# MCU.net
KiCad netlist of a schematic drawn in Altium Designer
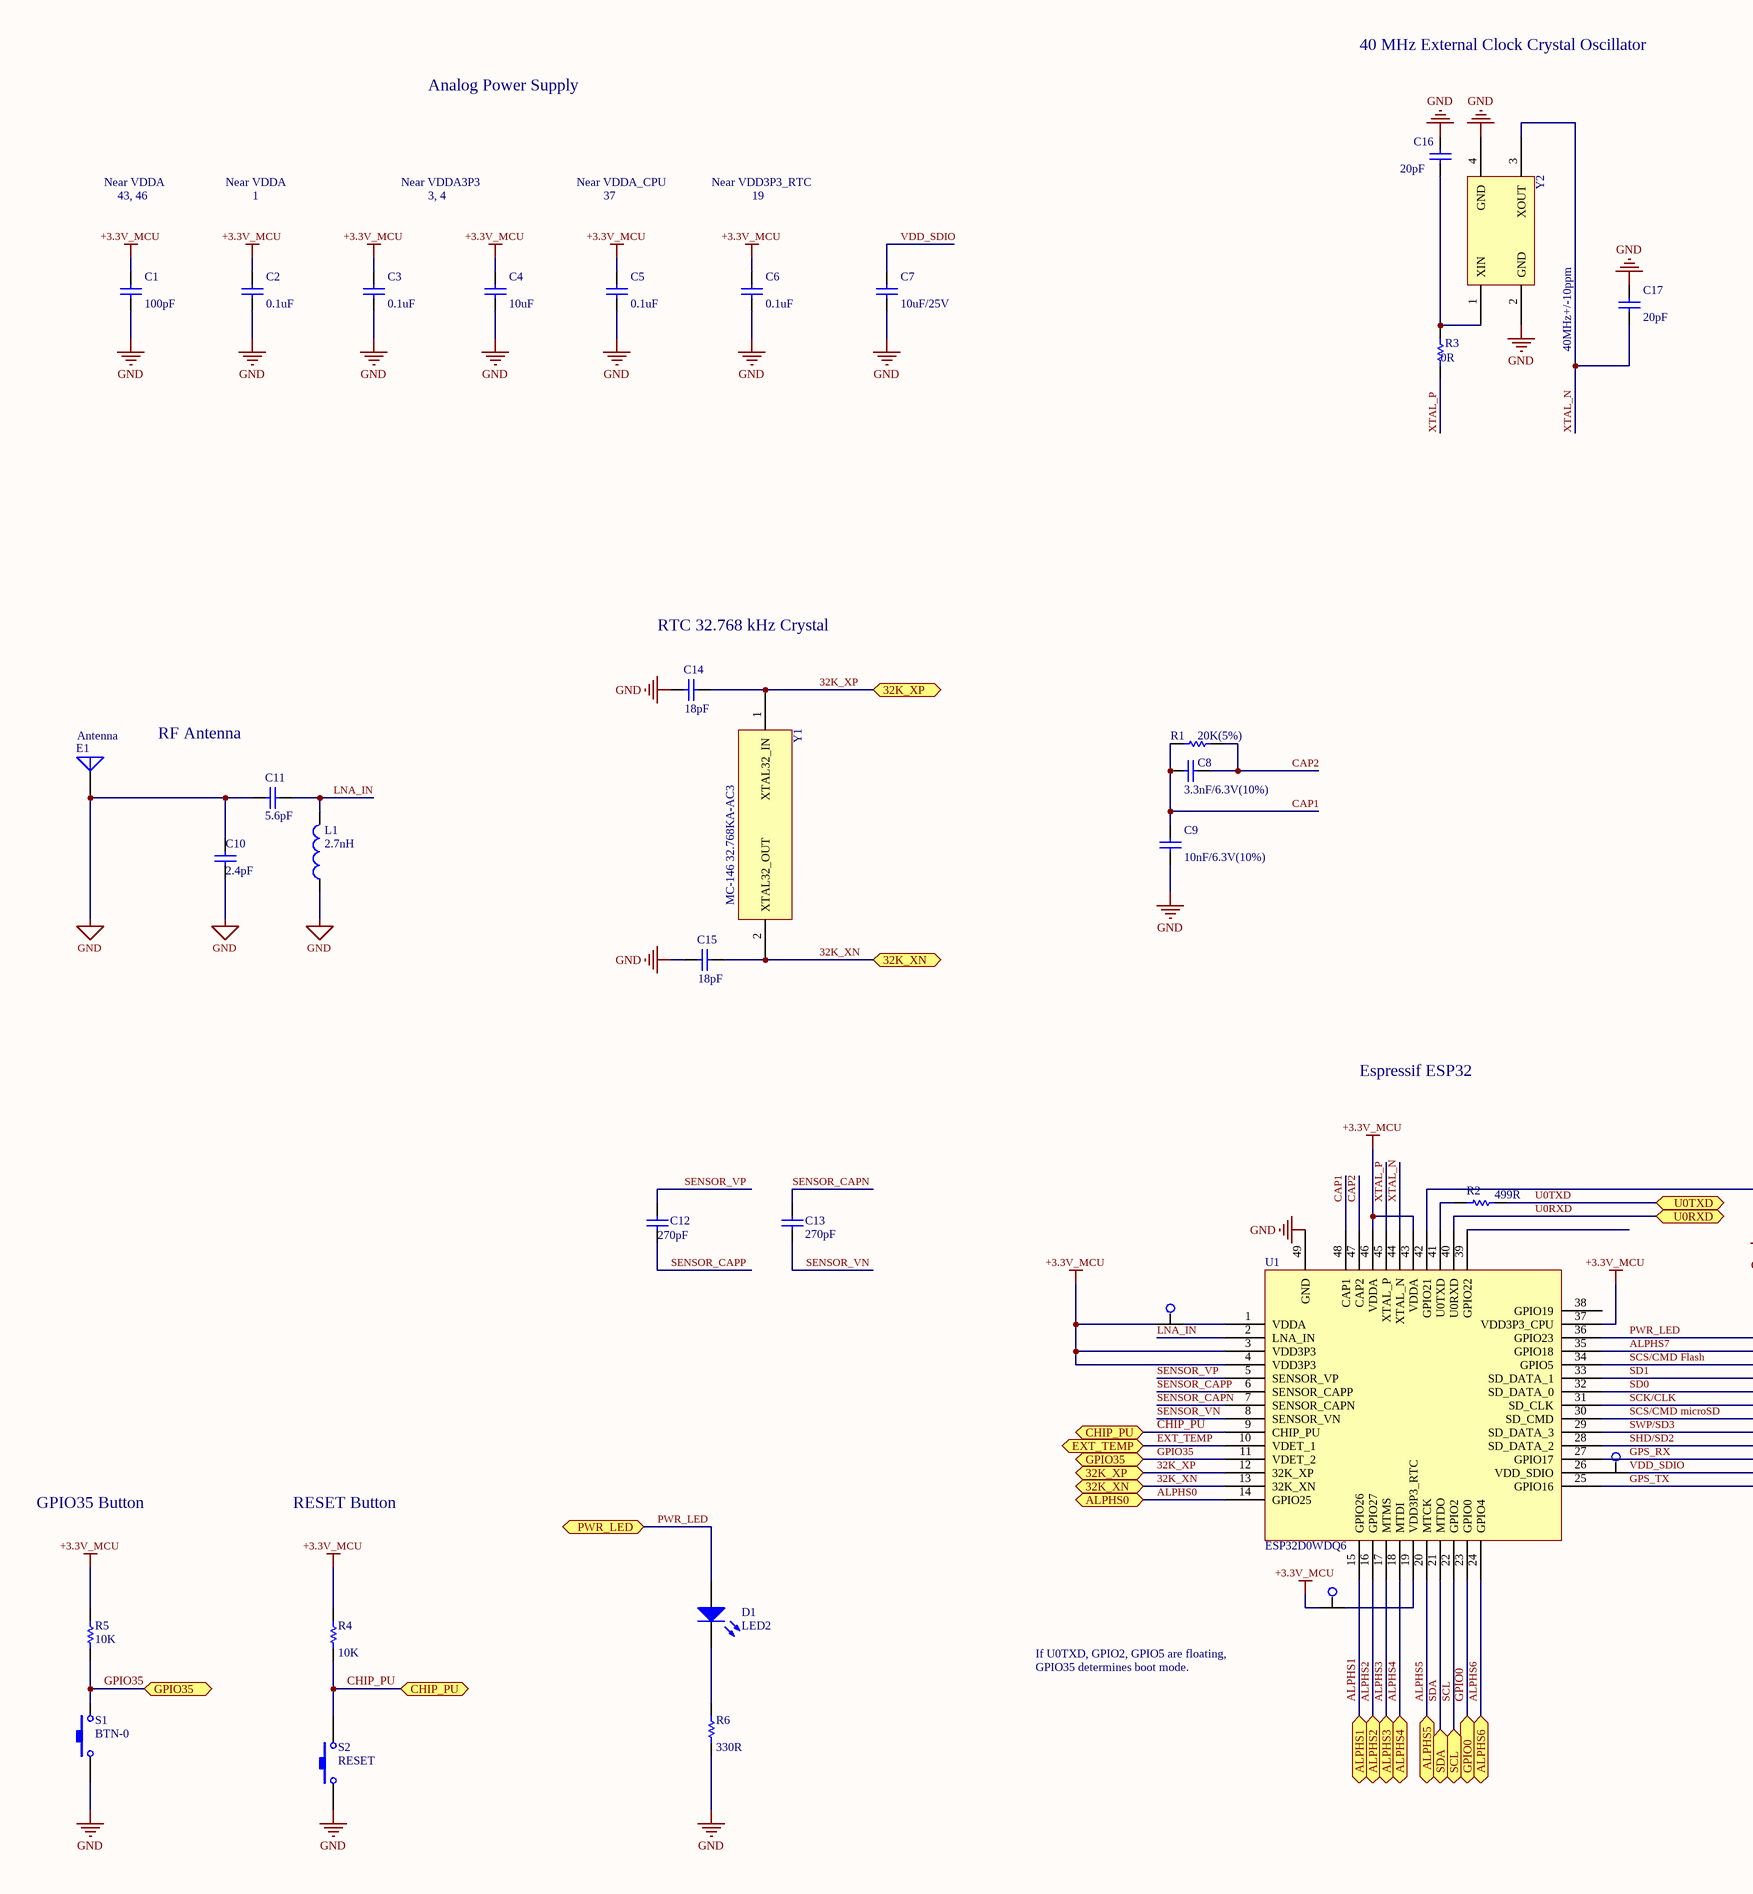
[diagram p0: MCU.SchDoc, left]
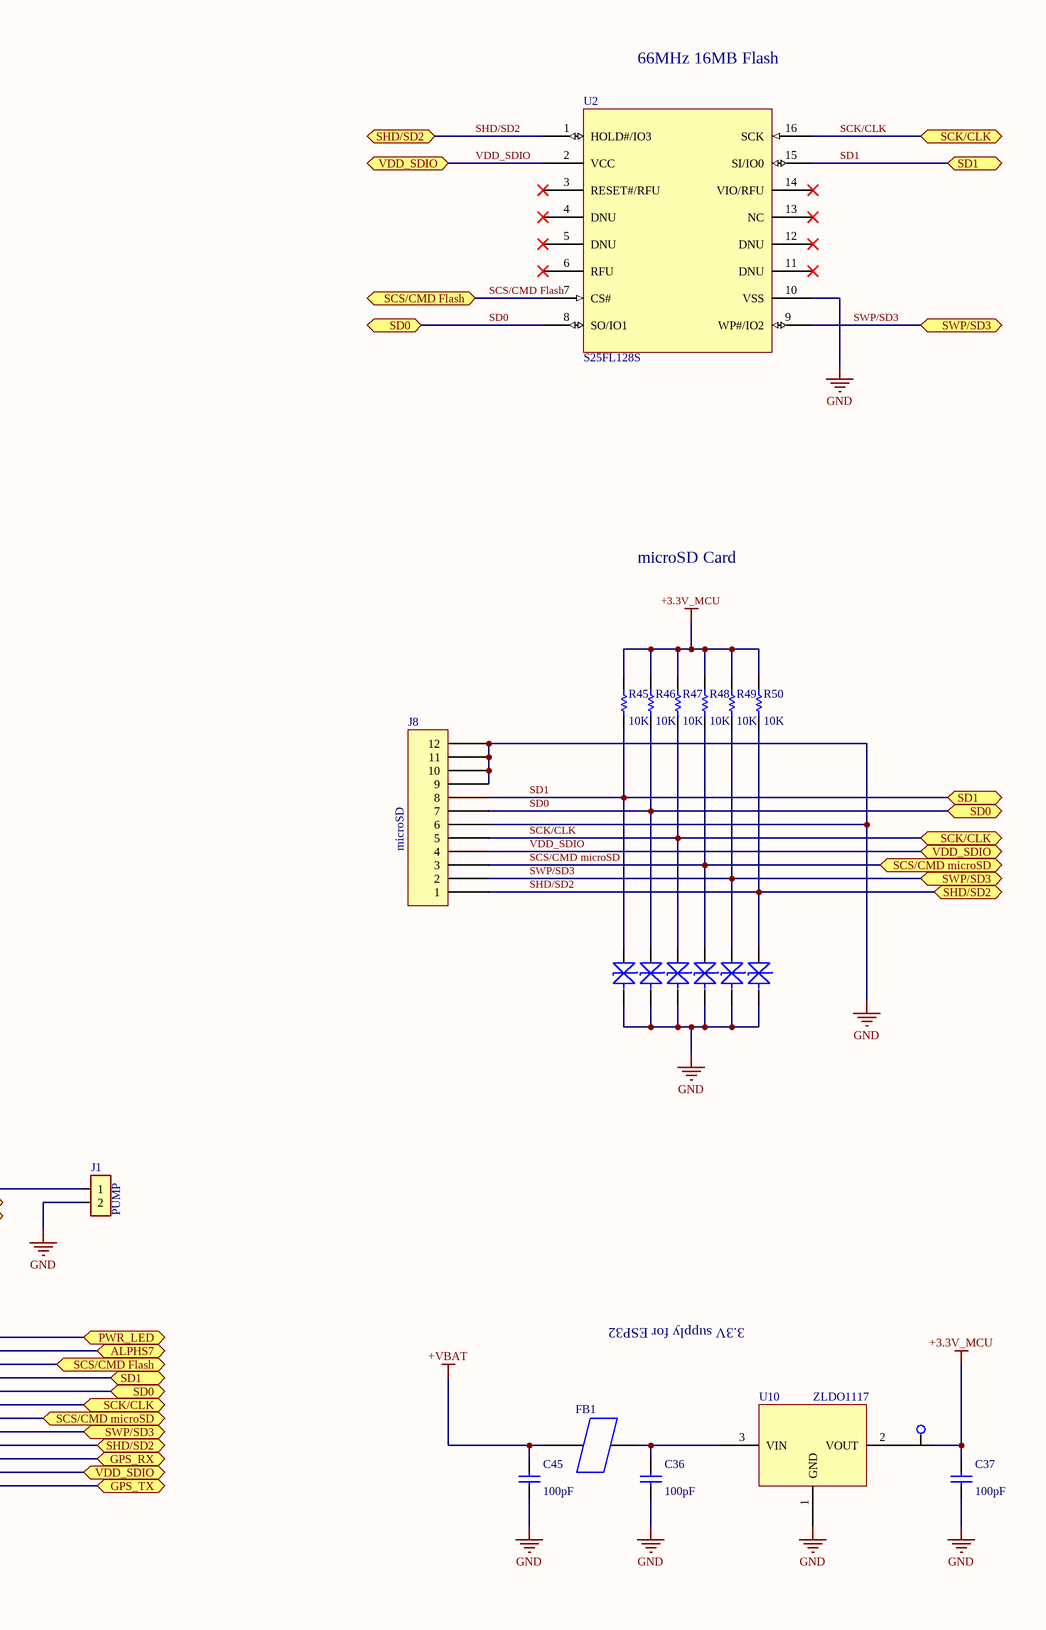
[diagram p1: MCU.SchDoc, right]

(export (version "E")
  (design (tool "Eeschema 10.0.6"))
  (components
    (comp (ref "C1")
      (value "100pF")
      (footprint "1608[0603]")
      (description "Capacitor")
      (fields (field (name "Comment") "Cap") (field (name "PUBLISHER") "Altium Limited"))
      (libsource (lib "Miscellaneous Devices") (part "Cap"))
    )
    (comp (ref "C2")
      (value "0.1uF")
      (footprint "1608[0603]")
      (description "Capacitor")
      (fields (field (name "Comment") "Cap") (field (name "PUBLISHER") "Altium Limited"))
      (libsource (lib "Miscellaneous Devices") (part "Cap"))
    )
    (comp (ref "C3")
      (value "0.1uF")
      (footprint "1608[0603]")
      (description "Capacitor")
      (fields (field (name "Comment") "Cap") (field (name "PUBLISHER") "Altium Limited"))
      (libsource (lib "Miscellaneous Devices") (part "Cap"))
    )
    (comp (ref "C4")
      (value "10uF")
      (footprint "1608[0603]")
      (description "Capacitor")
      (fields (field (name "Comment") "Cap") (field (name "PUBLISHER") "Altium Limited"))
      (libsource (lib "Miscellaneous Devices") (part "Cap"))
    )
    (comp (ref "C5")
      (value "0.1uF")
      (footprint "1608[0603]")
      (description "Capacitor")
      (fields (field (name "Comment") "Cap") (field (name "PUBLISHER") "Altium Limited"))
      (libsource (lib "Miscellaneous Devices") (part "Cap"))
    )
    (comp (ref "C6")
      (value "0.1uF")
      (footprint "1608[0603]")
      (description "Capacitor")
      (fields (field (name "Comment") "Cap") (field (name "PUBLISHER") "Altium Limited"))
      (libsource (lib "Miscellaneous Devices") (part "Cap"))
    )
    (comp (ref "C7")
      (value "10uF/25V")
      (footprint "1608[0603]")
      (description "Capacitor")
      (fields (field (name "Comment") "Cap") (field (name "PUBLISHER") "Altium Limited"))
      (libsource (lib "Miscellaneous Devices") (part "Cap"))
    )
    (comp (ref "C8")
      (value "3.3nF/6.3V(10%)")
      (footprint "1608[0603]")
      (description "Capacitor")
      (fields (field (name "Comment") "Cap") (field (name "PUBLISHER") "Altium Limited"))
      (libsource (lib "Miscellaneous Devices") (part "Cap"))
    )
    (comp (ref "C9")
      (value "10nF/6.3V(10%)")
      (footprint "1608[0603]")
      (description "Capacitor")
      (fields (field (name "Comment") "Cap") (field (name "PUBLISHER") "Altium Limited"))
      (libsource (lib "Miscellaneous Devices") (part "Cap"))
    )
    (comp (ref "C10")
      (value "2.4pF")
      (footprint "1608[0603]")
      (description "Capacitor")
      (fields (field (name "Comment") "Cap") (field (name "PUBLISHER") "Altium Limited"))
      (libsource (lib "Miscellaneous Devices") (part "Cap"))
    )
    (comp (ref "C11")
      (value "5.6pF")
      (footprint "1608[0603]")
      (description "Capacitor")
      (fields (field (name "Comment") "Cap") (field (name "PUBLISHER") "Altium Limited"))
      (libsource (lib "Miscellaneous Devices") (part "Cap"))
    )
    (comp (ref "C12")
      (value "270pF")
      (footprint "1608[0603]")
      (description "Capacitor")
      (fields (field (name "Comment") "Cap") (field (name "PUBLISHER") "Altium Limited"))
      (libsource (lib "Miscellaneous Devices") (part "Cap"))
    )
    (comp (ref "C13")
      (value "270pF")
      (footprint "1608[0603]")
      (description "Capacitor")
      (fields (field (name "Comment") "Cap") (field (name "PUBLISHER") "Altium Limited"))
      (libsource (lib "Miscellaneous Devices") (part "Cap"))
    )
    (comp (ref "C14")
      (value "18pF")
      (footprint "1608[0603]")
      (description "Capacitor")
      (fields (field (name "Comment") "Cap") (field (name "PUBLISHER") "Altium Limited"))
      (libsource (lib "Miscellaneous Devices") (part "Cap"))
    )
    (comp (ref "C15")
      (value "18pF")
      (footprint "1608[0603]")
      (description "Capacitor")
      (fields (field (name "Comment") "Cap") (field (name "PUBLISHER") "Altium Limited"))
      (libsource (lib "Miscellaneous Devices") (part "Cap"))
    )
    (comp (ref "C16")
      (value "20pF")
      (footprint "1608[0603]")
      (description "Capacitor")
      (fields (field (name "Comment") "Cap") (field (name "PUBLISHER") "Altium Limited"))
      (libsource (lib "Miscellaneous Devices") (part "Cap"))
    )
    (comp (ref "C17")
      (value "20pF")
      (footprint "1608[0603]")
      (description "Capacitor")
      (fields (field (name "Comment") "Cap") (field (name "PUBLISHER") "Altium Limited"))
      (libsource (lib "Miscellaneous Devices") (part "Cap"))
    )
    (comp (ref "C36")
      (value "100pF")
      (footprint "1608[0603]")
      (description "Capacitor")
      (fields (field (name "Comment") "Cap") (field (name "PUBLISHER") "Altium Limited"))
      (libsource (lib "Miscellaneous Devices") (part "Cap"))
    )
    (comp (ref "C37")
      (value "100pF")
      (footprint "1608[0603]")
      (description "Capacitor")
      (fields (field (name "Comment") "Cap") (field (name "PUBLISHER") "Altium Limited"))
      (libsource (lib "Miscellaneous Devices") (part "Cap"))
    )
    (comp (ref "C45")
      (value "100pF")
      (footprint "1608[0603]")
      (description "Capacitor")
      (fields (field (name "Comment") "Cap") (field (name "PUBLISHER") "Altium Limited"))
      (libsource (lib "Miscellaneous Devices") (part "Cap"))
    )
    (comp (ref "D1")
      (value "LED2")
      (footprint "3.2X1.6X1.1")
      (description "Typical RED, GREEN, YELLOW, AMBER GaAs LED")
      (fields (field (name "PUBLISHER") "Altium Limited"))
      (libsource (lib "Miscellaneous Devices") (part "LED2"))
    )
    (comp (ref "D4")
      (value "ESD7951ST5GOSCT-ND")
      (footprint "SODFL100X40-2N")
      (description "TVS Diode")
      (libsource (lib "Gas Monitor Components") (part "ESD7951S"))
    )
    (comp (ref "D5")
      (value "ESD7951ST5GOSCT-ND")
      (footprint "SODFL100X40-2N")
      (description "TVS Diode")
      (libsource (lib "Gas Monitor Components") (part "ESD7951S"))
    )
    (comp (ref "D6")
      (value "ESD7951ST5GOSCT-ND")
      (footprint "SODFL100X40-2N")
      (description "TVS Diode")
      (libsource (lib "Gas Monitor Components") (part "ESD7951S"))
    )
    (comp (ref "D7")
      (value "ESD7951ST5GOSCT-ND")
      (footprint "SODFL100X40-2N")
      (description "TVS Diode")
      (libsource (lib "Gas Monitor Components") (part "ESD7951S"))
    )
    (comp (ref "D8")
      (value "ESD7951ST5GOSCT-ND")
      (footprint "SODFL100X40-2N")
      (description "TVS Diode")
      (libsource (lib "Gas Monitor Components") (part "ESD7951S"))
    )
    (comp (ref "D9")
      (value "ESD7951ST5GOSCT-ND")
      (footprint "SODFL100X40-2N")
      (description "TVS Diode")
      (libsource (lib "Gas Monitor Components") (part "ESD7951S"))
    )
    (comp (ref "E1")
      (value "Antenna")
      (footprint "SWRA1117")
      (description "Generic Antenna")
      (fields (field (name "PUBLISHER") "Altium Limited"))
      (libsource (lib "Miscellaneous Devices") (part "Antenna"))
    )
    (comp (ref "FB1")
      (value "Ferrite Bead")
      (footprint "MI0805K400R-10")
      (description "MI0805K400R-10")
      (libsource (lib "Gas Monitor Components") (part "Ferrite Bead"))
    )
    (comp (ref "J1")
      (value "PUMP")
      (footprint "6410/2pin")
      (description "Connector 2 pin")
      (libsource (lib "VolcDB") (part "CON2"))
    )
    (comp (ref "J8")
      (value "microSD")
      (footprint "SD-47219-001")
      (libsource (lib "Gas Monitor Components") (part "CON12"))
    )
    (comp (ref "L1")
      (value "2.7nH")
      (footprint "INDC1608L")
      (description "Inductor")
      (fields (field (name "PUBLISHER") "Altium Limited"))
      (libsource (lib "Miscellaneous Devices") (part "Inductor"))
    )
    (comp (ref "R1")
      (value "20K(5%)")
      (footprint "6-0805_N")
      (description "Resistor")
      (fields (field (name "Comment") "Res1") (field (name "PUBLISHER") "Altium Limited"))
      (libsource (lib "Miscellaneous Devices") (part "Res1"))
    )
    (comp (ref "R2")
      (value "499R")
      (footprint "6-0805_L")
      (description "Resistor")
      (fields (field (name "Comment") "Res1") (field (name "PUBLISHER") "Altium Limited"))
      (libsource (lib "Miscellaneous Devices") (part "Res1"))
    )
    (comp (ref "R3")
      (value "0R")
      (footprint "6-0805_N")
      (description "Resistor")
      (fields (field (name "Comment") "Res1") (field (name "PUBLISHER") "Altium Limited"))
      (libsource (lib "Miscellaneous Devices") (part "Res1"))
    )
    (comp (ref "R4")
      (value "10K")
      (footprint "6-0805_N")
      (description "Resistor")
      (fields (field (name "Comment") "Res1") (field (name "PUBLISHER") "Altium Limited"))
      (libsource (lib "Miscellaneous Devices") (part "Res1"))
    )
    (comp (ref "R5")
      (value "10K")
      (footprint "6-0805_N")
      (description "Resistor")
      (fields (field (name "Comment") "Res1") (field (name "PUBLISHER") "Altium Limited"))
      (libsource (lib "Miscellaneous Devices") (part "Res1"))
    )
    (comp (ref "R6")
      (value "330R")
      (footprint "6-0805_N")
      (description "Resistor")
      (fields (field (name "Comment") "Res1") (field (name "PUBLISHER") "Altium Limited"))
      (libsource (lib "Miscellaneous Devices") (part "Res1"))
    )
    (comp (ref "R45")
      (value "10K")
      (footprint "6-0805_N")
      (description "Resistor")
      (fields (field (name "Comment") "Res1") (field (name "PUBLISHER") "Altium Limited"))
      (libsource (lib "Miscellaneous Devices") (part "Res1"))
    )
    (comp (ref "R46")
      (value "10K")
      (footprint "6-0805_N")
      (description "Resistor")
      (fields (field (name "Comment") "Res1") (field (name "PUBLISHER") "Altium Limited"))
      (libsource (lib "Miscellaneous Devices") (part "Res1"))
    )
    (comp (ref "R47")
      (value "10K")
      (footprint "6-0805_N")
      (description "Resistor")
      (fields (field (name "Comment") "Res1") (field (name "PUBLISHER") "Altium Limited"))
      (libsource (lib "Miscellaneous Devices") (part "Res1"))
    )
    (comp (ref "R48")
      (value "10K")
      (footprint "6-0805_N")
      (description "Resistor")
      (fields (field (name "Comment") "Res1") (field (name "PUBLISHER") "Altium Limited"))
      (libsource (lib "Miscellaneous Devices") (part "Res1"))
    )
    (comp (ref "R49")
      (value "10K")
      (footprint "6-0805_N")
      (description "Resistor")
      (fields (field (name "Comment") "Res1") (field (name "PUBLISHER") "Altium Limited"))
      (libsource (lib "Miscellaneous Devices") (part "Res1"))
    )
    (comp (ref "R50")
      (value "10K")
      (footprint "6-0805_N")
      (description "Resistor")
      (fields (field (name "Comment") "Res1") (field (name "PUBLISHER") "Altium Limited"))
      (libsource (lib "Miscellaneous Devices") (part "Res1"))
    )
    (comp (ref "S1")
      (value "BTN-0")
      (footprint "GPTS203211B")
      (description "Switch")
      (fields (field (name "PUBLISHER") "Altium Limited"))
      (libsource (lib "Miscellaneous Devices") (part "SW-PB"))
    )
    (comp (ref "S2")
      (value "RESET")
      (footprint "GPTS203211B")
      (description "Switch")
      (fields (field (name "PUBLISHER") "Altium Limited"))
      (libsource (lib "Miscellaneous Devices") (part "SW-PB"))
    )
    (comp (ref "TP15")
      (value "Hook Type Test Point")
      (footprint "36-500x-ND")
      (libsource (lib "Gas Monitor Components") (part "Hook Type Test Point"))
    )
    (comp (ref "TP22")
      (value "Hook Type Test Point")
      (footprint "36-500x-ND")
      (libsource (lib "Gas Monitor Components") (part "Hook Type Test Point"))
    )
    (comp (ref "TP23")
      (value "Hook Type Test Point")
      (footprint "36-500x-ND")
      (libsource (lib "Gas Monitor Components") (part "Hook Type Test Point"))
    )
    (comp (ref "TP24")
      (value "Hook Type Test Point")
      (footprint "36-500x-ND")
      (libsource (lib "Gas Monitor Components") (part "Hook Type Test Point"))
    )
    (comp (ref "U1")
      (value "ESP32D0WDQ6")
      (footprint "QFN40P600X600X90_HS-49N")
      (description "Microcontroller")
      (libsource (lib "Gas Monitor Components") (part "ESP32"))
    )
    (comp (ref "U2")
      (value "S25FL128S")
      (footprint "SOIC127P1030X265-16N")
      (description "QSPI 128M Flash Memory")
      (libsource (lib "Gas Monitor Components") (part "S25FL128S"))
    )
    (comp (ref "U10")
      (value "ZLDO1117")
      (footprint "SOT230P700X165-4N")
      (description "Linear Regulator 1A")
      (libsource (lib "Gas Monitor Components") (part "ZLDO1117"))
    )
    (comp (ref "Y1")
      (value "MC-146 32.768KA-AC3")
      (footprint "MC-146")
      (description "32.768 kHz Crystal")
      (libsource (lib "Gas Monitor Components") (part "MC-146 32.768KA-AC3"))
    )
    (comp (ref "Y2")
      (value "FA-20H")
      (footprint "FA-20H")
      (description "40MHz Crystal Oscillator")
      (libsource (lib "Gas Monitor Components") (part "Y1"))
    )
  )
  (nets
    (net (code "1") (name "+3.3V_MCU") (class "Default")
      (node (ref "C1") (pin "2") (pinfunction "2_2") (pintype "passive"))
      (node (ref "C2") (pin "2") (pinfunction "2_2") (pintype "passive"))
      (node (ref "C3") (pin "2") (pinfunction "2_2") (pintype "passive"))
      (node (ref "C37") (pin "1") (pinfunction "1_1") (pintype "passive"))
      (node (ref "C4") (pin "2") (pinfunction "2_2") (pintype "passive"))
      (node (ref "C5") (pin "2") (pinfunction "2_2") (pintype "passive"))
      (node (ref "C6") (pin "2") (pinfunction "2_2") (pintype "passive"))
      (node (ref "R4") (pin "2") (pinfunction "2_2") (pintype "passive"))
      (node (ref "R45") (pin "2") (pinfunction "2_2") (pintype "passive"))
      (node (ref "R46") (pin "2") (pinfunction "2_2") (pintype "passive"))
      (node (ref "R47") (pin "2") (pinfunction "2_2") (pintype "passive"))
      (node (ref "R48") (pin "2") (pinfunction "2_2") (pintype "passive"))
      (node (ref "R49") (pin "2") (pinfunction "2_2") (pintype "passive"))
      (node (ref "R5") (pin "2") (pinfunction "2_2") (pintype "passive"))
      (node (ref "R50") (pin "2") (pinfunction "2_2") (pintype "passive"))
      (node (ref "TP15") (pin "2") (pinfunction "2_2") (pintype "passive"))
      (node (ref "TP22") (pin "1") (pinfunction "1_1") (pintype "passive"))
      (node (ref "TP23") (pin "1") (pinfunction "1_1") (pintype "passive"))
      (node (ref "U1") (pin "3") (pinfunction "VDD3P3_3") (pintype "power_in"))
      (node (ref "U1") (pin "37") (pinfunction "VDD3P3_CPU_37") (pintype "passive"))
      (node (ref "U1") (pin "4") (pinfunction "VDD3P3_4") (pintype "passive"))
      (node (ref "U1") (pin "43") (pinfunction "VDDA_43") (pintype "power_in"))
      (node (ref "U1") (pin "46") (pinfunction "VDDA_46") (pintype "power_in"))
    )
    (net (code "2") (name "+VBAT") (class "Default")
      (node (ref "C45") (pin "2") (pinfunction "2_2") (pintype "passive"))
      (node (ref "FB1") (pin "1") (pinfunction "1_1") (pintype "passive"))
    )
    (net (code "3") (name "/32K_XN") (class "Default")
      (node (ref "C15") (pin "2") (pinfunction "2_2") (pintype "passive"))
      (node (ref "U1") (pin "13") (pinfunction "32K_XN_13") (pintype "passive"))
      (node (ref "Y1") (pin "2") (pinfunction "XTAL32_OUT_2") (pintype "passive"))
    )
    (net (code "4") (name "/32K_XP") (class "Default")
      (node (ref "C14") (pin "2") (pinfunction "2_2") (pintype "passive"))
      (node (ref "U1") (pin "12") (pinfunction "32K_XP_12") (pintype "passive"))
      (node (ref "Y1") (pin "1") (pinfunction "XTAL32_IN_1") (pintype "passive"))
    )
    (net (code "5") (name "/ALPHS0") (class "Default")
      (node (ref "U1") (pin "14") (pinfunction "GPIO25_14") (pintype "passive"))
    )
    (net (code "6") (name "/ALPHS1") (class "Default")
      (node (ref "U1") (pin "15") (pinfunction "GPIO26_15") (pintype "passive"))
    )
    (net (code "7") (name "/ALPHS2") (class "Default")
      (node (ref "U1") (pin "16") (pinfunction "GPIO27_16") (pintype "passive"))
    )
    (net (code "8") (name "/ALPHS3") (class "Default")
      (node (ref "U1") (pin "17") (pinfunction "MTMS_17") (pintype "passive"))
    )
    (net (code "9") (name "/ALPHS4") (class "Default")
      (node (ref "U1") (pin "18") (pinfunction "MTDI_18") (pintype "passive"))
    )
    (net (code "10") (name "/ALPHS5") (class "Default")
      (node (ref "U1") (pin "20") (pinfunction "MTCK_20") (pintype "passive"))
    )
    (net (code "11") (name "/ALPHS6") (class "Default")
      (node (ref "U1") (pin "24") (pinfunction "GPIO4_24") (pintype "passive"))
    )
    (net (code "12") (name "/ALPHS7") (class "Default")
      (node (ref "U1") (pin "35") (pinfunction "GPIO18_35") (pintype "passive"))
    )
    (net (code "13") (name "/CAP1") (class "Default")
      (node (ref "C8") (pin "2") (pinfunction "2_2") (pintype "passive"))
      (node (ref "C9") (pin "2") (pinfunction "2_2") (pintype "passive"))
      (node (ref "R1") (pin "1") (pinfunction "1_1") (pintype "passive"))
      (node (ref "U1") (pin "48") (pinfunction "CAP1_48") (pintype "passive"))
    )
    (net (code "14") (name "/CAP2") (class "Default")
      (node (ref "C8") (pin "1") (pinfunction "1_1") (pintype "passive"))
      (node (ref "R1") (pin "2") (pinfunction "2_2") (pintype "passive"))
      (node (ref "U1") (pin "47") (pinfunction "CAP2_47") (pintype "passive"))
    )
    (net (code "15") (name "/CHIP_PU") (class "Default")
      (node (ref "R4") (pin "1") (pinfunction "1_1") (pintype "passive"))
      (node (ref "S2") (pin "2") (pinfunction "2_2") (pintype "passive"))
      (node (ref "U1") (pin "9") (pinfunction "CHIP_PU_9") (pintype "passive"))
    )
    (net (code "16") (name "/EXT_TEMP") (class "Default")
      (node (ref "U1") (pin "10") (pinfunction "VDET_1_10") (pintype "passive"))
    )
    (net (code "17") (name "/GPIO0") (class "Default")
      (node (ref "U1") (pin "23") (pinfunction "GPIO0_23") (pintype "passive"))
    )
    (net (code "18") (name "/GPIO35") (class "Default")
      (node (ref "R5") (pin "1") (pinfunction "1_1") (pintype "passive"))
      (node (ref "S1") (pin "2") (pinfunction "2_2") (pintype "passive"))
      (node (ref "U1") (pin "11") (pinfunction "VDET_2_11") (pintype "passive"))
    )
    (net (code "19") (name "/GPS_RX") (class "Default")
      (node (ref "U1") (pin "27") (pinfunction "GPIO17_27") (pintype "passive"))
    )
    (net (code "20") (name "/GPS_TX") (class "Default")
      (node (ref "U1") (pin "25") (pinfunction "GPIO16_25") (pintype "passive"))
    )
    (net (code "21") (name "/LNA_IN") (class "Default")
      (node (ref "C11") (pin "1") (pinfunction "1_1") (pintype "passive"))
      (node (ref "L1") (pin "2") (pinfunction "2_2") (pintype "passive"))
      (node (ref "U1") (pin "2") (pinfunction "LNA_IN_2") (pintype "passive"))
    )
    (net (code "22") (name "/PWR_LED") (class "Default")
      (node (ref "D1") (pin "1") (pinfunction "A_1") (pintype "passive"))
      (node (ref "U1") (pin "36") (pinfunction "GPIO23_36") (pintype "passive"))
    )
    (net (code "23") (name "/SCK{slash}CLK") (class "Default")
      (node (ref "D6") (pin "2") (pinfunction "ANODE_2") (pintype "passive"))
      (node (ref "J8") (pin "5") (pinfunction "5_5") (pintype "passive"))
      (node (ref "R47") (pin "1") (pinfunction "1_1") (pintype "passive"))
      (node (ref "U1") (pin "31") (pinfunction "SD_CLK_31") (pintype "passive"))
      (node (ref "U2") (pin "16") (pinfunction "SCK_16") (pintype "input"))
    )
    (net (code "24") (name "/SCL") (class "Default")
      (node (ref "U1") (pin "22") (pinfunction "GPIO2_22") (pintype "passive"))
    )
    (net (code "25") (name "/SCS{slash}CMD Flash") (class "Default")
      (node (ref "U1") (pin "34") (pinfunction "GPIO5_34") (pintype "passive"))
      (node (ref "U2") (pin "7") (pinfunction "CS#_7") (pintype "input"))
    )
    (net (code "26") (name "/SCS{slash}CMD microSD") (class "Default")
      (node (ref "D7") (pin "2") (pinfunction "ANODE_2") (pintype "passive"))
      (node (ref "J8") (pin "3") (pinfunction "3_3") (pintype "passive"))
      (node (ref "R48") (pin "1") (pinfunction "1_1") (pintype "passive"))
      (node (ref "U1") (pin "30") (pinfunction "SD_CMD_30") (pintype "passive"))
    )
    (net (code "27") (name "/SD0") (class "Default")
      (node (ref "D5") (pin "2") (pinfunction "ANODE_2") (pintype "passive"))
      (node (ref "J8") (pin "7") (pinfunction "7_7") (pintype "passive"))
      (node (ref "R46") (pin "1") (pinfunction "1_1") (pintype "passive"))
      (node (ref "U1") (pin "32") (pinfunction "SD_DATA_0_32") (pintype "passive"))
      (node (ref "U2") (pin "8") (pinfunction "SO/IO1_8") (pintype "bidirectional"))
    )
    (net (code "28") (name "/SD1") (class "Default")
      (node (ref "D4") (pin "2") (pinfunction "ANODE_2") (pintype "passive"))
      (node (ref "J8") (pin "8") (pinfunction "8_8") (pintype "passive"))
      (node (ref "R45") (pin "1") (pinfunction "1_1") (pintype "passive"))
      (node (ref "U1") (pin "33") (pinfunction "SD_DATA_1_33") (pintype "passive"))
      (node (ref "U2") (pin "15") (pinfunction "SI/IO0_15") (pintype "bidirectional"))
    )
    (net (code "29") (name "/SDA") (class "Default")
      (node (ref "U1") (pin "21") (pinfunction "MTDO_21") (pintype "passive"))
    )
    (net (code "30") (name "/SENSOR_CAPN") (class "Default")
      (node (ref "C13") (pin "1") (pinfunction "1_1") (pintype "passive"))
      (node (ref "U1") (pin "7") (pinfunction "SENSOR_CAPN_7") (pintype "passive"))
    )
    (net (code "31") (name "/SENSOR_CAPP") (class "Default")
      (node (ref "C12") (pin "1") (pinfunction "1_1") (pintype "passive"))
      (node (ref "U1") (pin "6") (pinfunction "SENSOR_CAPP_6") (pintype "passive"))
    )
    (net (code "32") (name "/SENSOR_VN") (class "Default")
      (node (ref "C13") (pin "2") (pinfunction "2_2") (pintype "passive"))
      (node (ref "U1") (pin "8") (pinfunction "SENSOR_VN_8") (pintype "passive"))
    )
    (net (code "33") (name "/SENSOR_VP") (class "Default")
      (node (ref "C12") (pin "2") (pinfunction "2_2") (pintype "passive"))
      (node (ref "U1") (pin "5") (pinfunction "SENSOR_VP_5") (pintype "passive"))
    )
    (net (code "34") (name "/SHD{slash}SD2") (class "Default")
      (node (ref "D9") (pin "2") (pinfunction "ANODE_2") (pintype "passive"))
      (node (ref "J8") (pin "1") (pinfunction "1_1") (pintype "passive"))
      (node (ref "R50") (pin "1") (pinfunction "1_1") (pintype "passive"))
      (node (ref "U1") (pin "28") (pinfunction "SD_DATA_2_28") (pintype "passive"))
      (node (ref "U2") (pin "1") (pinfunction "HOLD#/IO3_1") (pintype "bidirectional"))
    )
    (net (code "35") (name "/SWP{slash}SD3") (class "Default")
      (node (ref "D8") (pin "2") (pinfunction "ANODE_2") (pintype "passive"))
      (node (ref "J8") (pin "2") (pinfunction "2_2") (pintype "passive"))
      (node (ref "R49") (pin "1") (pinfunction "1_1") (pintype "passive"))
      (node (ref "U1") (pin "29") (pinfunction "SD_DATA_3_29") (pintype "passive"))
      (node (ref "U2") (pin "9") (pinfunction "WP#/IO2_9") (pintype "bidirectional"))
    )
    (net (code "36") (name "/U0RXD") (class "Default")
      (node (ref "U1") (pin "40") (pinfunction "U0RXD_40") (pintype "passive"))
    )
    (net (code "37") (name "/U0TXD") (class "Default")
      (node (ref "R2") (pin "2") (pinfunction "2_2") (pintype "passive"))
    )
    (net (code "38") (name "/VDD_SDIO") (class "Default")
      (node (ref "C7") (pin "2") (pinfunction "2_2") (pintype "passive"))
      (node (ref "J8") (pin "4") (pinfunction "4_4") (pintype "passive"))
      (node (ref "TP24") (pin "2") (pinfunction "2_2") (pintype "passive"))
      (node (ref "U2") (pin "2") (pinfunction "VCC_2") (pintype "power_in"))
    )
    (net (code "39") (name "/XTAL_N") (class "Default")
      (node (ref "C17") (pin "1") (pinfunction "1_1") (pintype "passive"))
      (node (ref "U1") (pin "44") (pinfunction "XTAL_N_44") (pintype "passive"))
      (node (ref "Y2") (pin "3") (pinfunction "XOUT_3") (pintype "passive"))
    )
    (net (code "40") (name "/XTAL_P") (class "Default")
      (node (ref "R3") (pin "1") (pinfunction "1_1") (pintype "passive"))
      (node (ref "U1") (pin "45") (pinfunction "XTAL_P_45") (pintype "passive"))
    )
    (net (code "41") (name "GND") (class "Default")
      (node (ref "C1") (pin "1") (pinfunction "1_1") (pintype "passive"))
      (node (ref "C10") (pin "1") (pinfunction "1_1") (pintype "passive"))
      (node (ref "C10") (pin "2") (pinfunction "2_2") (pintype "passive"))
      (node (ref "C11") (pin "2") (pinfunction "2_2") (pintype "passive"))
      (node (ref "C14") (pin "1") (pinfunction "1_1") (pintype "passive"))
      (node (ref "C15") (pin "1") (pinfunction "1_1") (pintype "passive"))
      (node (ref "C16") (pin "2") (pinfunction "2_2") (pintype "passive"))
      (node (ref "C17") (pin "2") (pinfunction "2_2") (pintype "passive"))
      (node (ref "C2") (pin "1") (pinfunction "1_1") (pintype "passive"))
      (node (ref "C3") (pin "1") (pinfunction "1_1") (pintype "passive"))
      (node (ref "C36") (pin "1") (pinfunction "1_1") (pintype "passive"))
      (node (ref "C37") (pin "2") (pinfunction "2_2") (pintype "passive"))
      (node (ref "C4") (pin "1") (pinfunction "1_1") (pintype "passive"))
      (node (ref "C45") (pin "1") (pinfunction "1_1") (pintype "passive"))
      (node (ref "C5") (pin "1") (pinfunction "1_1") (pintype "passive"))
      (node (ref "C6") (pin "1") (pinfunction "1_1") (pintype "passive"))
      (node (ref "C7") (pin "1") (pinfunction "1_1") (pintype "passive"))
      (node (ref "C9") (pin "1") (pinfunction "1_1") (pintype "passive"))
      (node (ref "D4") (pin "1") (pinfunction "CATHODE_1") (pintype "passive"))
      (node (ref "D5") (pin "1") (pinfunction "CATHODE_1") (pintype "passive"))
      (node (ref "D6") (pin "1") (pinfunction "CATHODE_1") (pintype "passive"))
      (node (ref "D7") (pin "1") (pinfunction "CATHODE_1") (pintype "passive"))
      (node (ref "D8") (pin "1") (pinfunction "CATHODE_1") (pintype "passive"))
      (node (ref "D9") (pin "1") (pinfunction "CATHODE_1") (pintype "passive"))
      (node (ref "E1") (pin "1") (pinfunction "A_1") (pintype "passive"))
      (node (ref "J1") (pin "2") (pinfunction "2_2") (pintype "passive"))
      (node (ref "J8") (pin "10") (pinfunction "10_10") (pintype "passive"))
      (node (ref "J8") (pin "11") (pinfunction "11_11") (pintype "passive"))
      (node (ref "J8") (pin "12") (pinfunction "12_12") (pintype "passive"))
      (node (ref "J8") (pin "6") (pinfunction "6_6") (pintype "passive"))
      (node (ref "J8") (pin "9") (pinfunction "9_9") (pintype "passive"))
      (node (ref "L1") (pin "1") (pinfunction "1_1") (pintype "passive"))
      (node (ref "R6") (pin "1") (pinfunction "1_1") (pintype "passive"))
      (node (ref "S1") (pin "1") (pinfunction "1_1") (pintype "passive"))
      (node (ref "S2") (pin "1") (pinfunction "1_1") (pintype "passive"))
      (node (ref "U1") (pin "49") (pinfunction "GND_49") (pintype "power_in"))
      (node (ref "U10") (pin "1") (pinfunction "GND_1") (pintype "power_in"))
      (node (ref "U2") (pin "10") (pinfunction "VSS_10") (pintype "power_in"))
      (node (ref "Y2") (pin "2") (pinfunction "GND_2") (pintype "power_in"))
      (node (ref "Y2") (pin "4") (pinfunction "GND_4") (pintype "power_in"))
    )
    (net (code "42") (name "Net-(D1-K)") (class "Default")
      (node (ref "D1") (pin "2") (pinfunction "K_2") (pintype "passive"))
      (node (ref "R6") (pin "2") (pinfunction "2_2") (pintype "passive"))
    )
    (net (code "43") (name "Net-(TP22-Pad2)") (class "Default")
      (node (ref "TP22") (pin "2") (pinfunction "2_2") (pintype "passive"))
      (node (ref "U1") (pin "1") (pinfunction "VDDA_1") (pintype "power_in"))
    )
    (net (code "44") (name "Net-(U1-GPIO21)") (class "Default")
      (node (ref "J1") (pin "1") (pinfunction "1_1") (pintype "passive"))
      (node (ref "U1") (pin "42") (pinfunction "GPIO21_42") (pintype "passive"))
    )
    (net (code "45") (name "Net-(U1-U0TXD)") (class "Default")
      (node (ref "R2") (pin "1") (pinfunction "1_1") (pintype "passive"))
      (node (ref "U1") (pin "41") (pinfunction "U0TXD_41") (pintype "passive"))
    )
    (net (code "46") (name "Net-(U1-VDD3P3_RTC)") (class "Default")
      (node (ref "TP23") (pin "2") (pinfunction "2_2") (pintype "passive"))
      (node (ref "U1") (pin "19") (pinfunction "VDD3P3_RTC_19") (pintype "passive"))
    )
    (net (code "47") (name "Net-(U1-VDD_SDIO)") (class "Default")
      (node (ref "TP24") (pin "1") (pinfunction "1_1") (pintype "passive"))
      (node (ref "U1") (pin "26") (pinfunction "VDD_SDIO_26") (pintype "passive"))
    )
    (net (code "48") (name "Net-(U10-VIN)") (class "Default")
      (node (ref "C36") (pin "2") (pinfunction "2_2") (pintype "passive"))
      (node (ref "FB1") (pin "2") (pinfunction "2_2") (pintype "passive"))
      (node (ref "U10") (pin "3") (pinfunction "VIN_3") (pintype "power_in"))
    )
    (net (code "49") (name "Net-(U10-VOUT)") (class "Default")
      (node (ref "TP15") (pin "1") (pinfunction "1_1") (pintype "passive"))
      (node (ref "U10") (pin "2") (pinfunction "VOUT_2") (pintype "power_in"))
    )
    (net (code "50") (name "Net-(Y2-XIN)") (class "Default")
      (node (ref "C16") (pin "1") (pinfunction "1_1") (pintype "passive"))
      (node (ref "R3") (pin "2") (pinfunction "2_2") (pintype "passive"))
      (node (ref "Y2") (pin "1") (pinfunction "XIN_1") (pintype "passive"))
    )
    (net (code "51") (name "unconnected-(U1-GPIO19-Pad38)") (class "Default")
      (node (ref "U1") (pin "38") (pinfunction "GPIO19_38") (pintype "passive"))
    )
    (net (code "52") (name "unconnected-(U1-GPIO22-Pad39)") (class "Default")
      (node (ref "U1") (pin "39") (pinfunction "GPIO22_39") (pintype "passive"))
    )
    (net (code "53") (name "unconnected-(U2-DNU-Pad4)") (class "Default")
      (node (ref "U2") (pin "4") (pinfunction "DNU_4") (pintype "passive+no_connect"))
    )
    (net (code "54") (name "unconnected-(U2-DNU-Pad5)") (class "Default")
      (node (ref "U2") (pin "5") (pinfunction "DNU_5") (pintype "passive+no_connect"))
    )
    (net (code "55") (name "unconnected-(U2-DNU-Pad11)") (class "Default")
      (node (ref "U2") (pin "11") (pinfunction "DNU_11") (pintype "passive+no_connect"))
    )
    (net (code "56") (name "unconnected-(U2-DNU-Pad12)") (class "Default")
      (node (ref "U2") (pin "12") (pinfunction "DNU_12") (pintype "passive+no_connect"))
    )
    (net (code "57") (name "unconnected-(U2-NC-Pad13)") (class "Default")
      (node (ref "U2") (pin "13") (pinfunction "NC_13") (pintype "passive+no_connect"))
    )
    (net (code "58") (name "unconnected-(U2-RESET#{slash}RFU-Pad3)") (class "Default")
      (node (ref "U2") (pin "3") (pinfunction "RESET#/RFU_3") (pintype "passive+no_connect"))
    )
    (net (code "59") (name "unconnected-(U2-RFU-Pad6)") (class "Default")
      (node (ref "U2") (pin "6") (pinfunction "RFU_6") (pintype "passive+no_connect"))
    )
    (net (code "60") (name "unconnected-(U2-VIO{slash}RFU-Pad14)") (class "Default")
      (node (ref "U2") (pin "14") (pinfunction "VIO/RFU_14") (pintype "power_in+no_connect"))
    )
  )
)
